# 02.net
KiCad netlist of a schematic drawn in Altium Designer
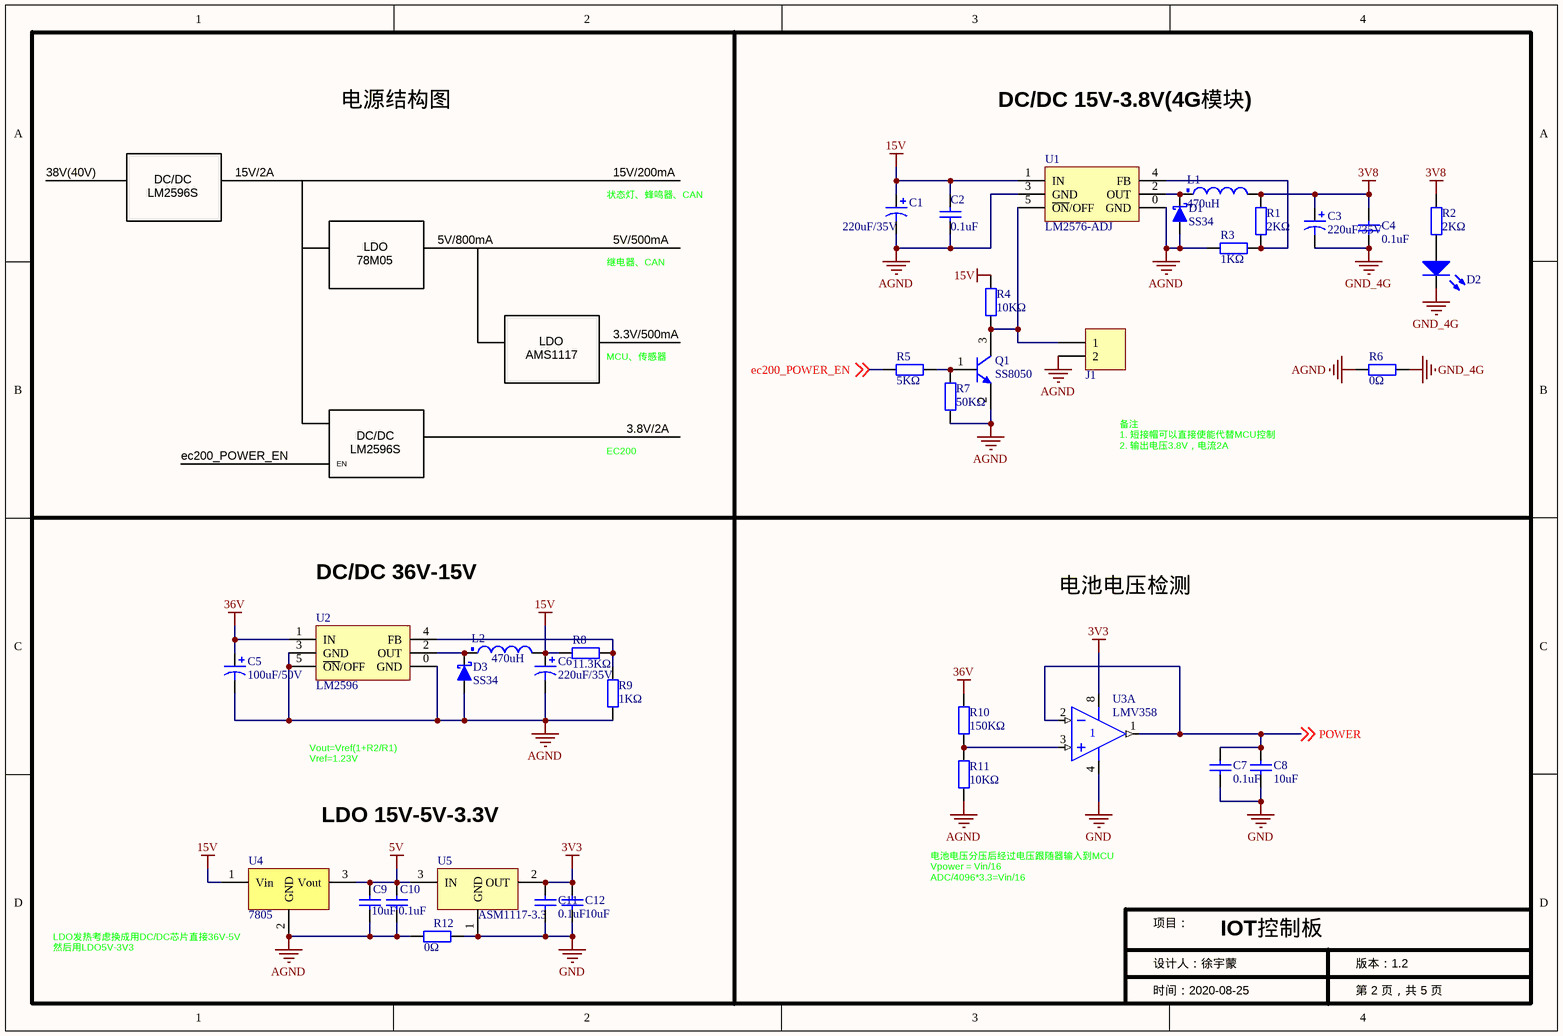
[diagram p0: 02_电源部分.SchDoc]

(export (version "E")
  (design (tool "Eeschema 10.0.6"))
  (components
    (comp (ref "C1")
      (value "220uF/35V")
      (footprint "Cap8x10.5mm")
      (description "贴片电解电容 8*10.5mm")
      (fields (field (name "Comment") "Cap Pol") (field (name "PUBLISHER") "Altium Limited"))
      (libsource (lib "元件库") (part "Cap Pol"))
    )
    (comp (ref "C2")
      (value "0.1uF")
      (footprint "CAP-0603")
      (description "无极性电容")
      (fields (field (name "Comment") "Cap") (field (name "PUBLISHER") "Altium Limited"))
      (libsource (lib "Arrowy_Racing") (part "Cap"))
    )
    (comp (ref "C3")
      (value "220uF/35V")
      (footprint "Cap8x10.5mm")
      (description "贴片电解电容 8*10.5mm")
      (fields (field (name "Comment") "Cap Pol") (field (name "PUBLISHER") "Altium Limited"))
      (libsource (lib "元件库") (part "Cap Pol"))
    )
    (comp (ref "C4")
      (value "0.1uF")
      (footprint "CAP-0603")
      (description "无极性电容")
      (fields (field (name "Comment") "Cap") (field (name "PUBLISHER") "Altium Limited"))
      (libsource (lib "Arrowy_Racing") (part "Cap"))
    )
    (comp (ref "C5")
      (value "100uF/50V")
      (footprint "Cap8x10.5mm")
      (description "贴片电解电容 8*10.5mm")
      (fields (field (name "Comment") "Cap Pol") (field (name "PUBLISHER") "Altium Limited"))
      (libsource (lib "元件库") (part "Cap Pol"))
    )
    (comp (ref "C6")
      (value "220uF/35V")
      (footprint "Cap8x10.5mm")
      (description "贴片电解电容 8*10.5mm")
      (fields (field (name "Comment") "Cap Pol") (field (name "PUBLISHER") "Altium Limited"))
      (libsource (lib "元件库") (part "Cap Pol"))
    )
    (comp (ref "C7")
      (value "0.1uF")
      (footprint "CAP-0603")
      (description "无极性电容")
      (fields (field (name "Comment") "Cap") (field (name "PUBLISHER") "Altium Limited"))
      (libsource (lib "Arrowy_Racing") (part "Cap"))
    )
    (comp (ref "C8")
      (value "10uF")
      (footprint "CAP-0603")
      (description "无极性电容")
      (fields (field (name "Comment") "Cap") (field (name "PUBLISHER") "Altium Limited"))
      (libsource (lib "Arrowy_Racing") (part "Cap"))
    )
    (comp (ref "C9")
      (value "10uF")
      (footprint "CAP-0603")
      (description "无极性电容")
      (fields (field (name "Comment") "Cap") (field (name "PUBLISHER") "Altium Limited"))
      (libsource (lib "Arrowy_Racing") (part "Cap"))
    )
    (comp (ref "C10")
      (value "0.1uF")
      (footprint "CAP-0603")
      (description "无极性电容")
      (fields (field (name "Comment") "Cap") (field (name "PUBLISHER") "Altium Limited"))
      (libsource (lib "Arrowy_Racing") (part "Cap"))
    )
    (comp (ref "C11")
      (value "0.1uF")
      (footprint "CAP-0603")
      (description "无极性电容")
      (fields (field (name "Comment") "Cap") (field (name "PUBLISHER") "Altium Limited"))
      (libsource (lib "Arrowy_Racing") (part "Cap"))
    )
    (comp (ref "C12")
      (value "10uF")
      (footprint "CAP-0603")
      (description "无极性电容")
      (fields (field (name "Comment") "Cap") (field (name "PUBLISHER") "Altium Limited"))
      (libsource (lib "Arrowy_Racing") (part "Cap"))
    )
    (comp (ref "D1")
      (value "SS34")
      (footprint "SMA(DO-214AC)")
      (description "Schottky Diode")
      (fields (field (name "PUBLISHER") "Altium Limited"))
      (libsource (lib "元件库") (part "D Schottky"))
    )
    (comp (ref "D2")
      (value "LED")
      (footprint "LED_0805")
      (description "发光二极管")
      (fields (field (name "PUBLISHER") "Altium Limited"))
      (libsource (lib "Arrowy_Racing") (part "LED"))
    )
    (comp (ref "D3")
      (value "SS34")
      (footprint "SMA(DO-214AC)")
      (description "Schottky Diode")
      (fields (field (name "PUBLISHER") "Altium Limited"))
      (libsource (lib "元件库") (part "D Schottky"))
    )
    (comp (ref "J1")
      (value "Header 2")
      (footprint "Header_2X1_2.54")
      (description "接插件")
      (fields (field (name "PUBLISHER") "Altium Limited"))
      (libsource (lib "Arrowy_Racing") (part "Header 2"))
    )
    (comp (ref "L1")
      (value "470uH")
      (footprint "CD43")
      (description "贴片功率电感")
      (fields (field (name "Comment") "Inductor") (field (name "PUBLISHER") "Altium Limited"))
      (libsource (lib "元件库") (part "Inductor"))
    )
    (comp (ref "L2")
      (value "470uH")
      (footprint "CD43")
      (description "贴片功率电感")
      (fields (field (name "Comment") "Inductor") (field (name "PUBLISHER") "Altium Limited"))
      (libsource (lib "元件库") (part "Inductor"))
    )
    (comp (ref "Q1")
      (value "SS8050")
      (footprint "SOT-23")
      (description "NPN贴片三极管")
      (fields (field (name "PUBLISHER") "Altium Limited"))
      (libsource (lib "Arrowy_Racing") (part "SS8050"))
    )
    (comp (ref "R1")
      (value "2KΩ")
      (footprint "0603")
      (description "贴片电阻")
      (fields (field (name "Comment") "Res") (field (name "PUBLISHER") "Altium Limited"))
      (libsource (lib "") (part "Res_2"))
    )
    (comp (ref "R2")
      (value "2KΩ")
      (footprint "0603")
      (description "贴片电阻")
      (fields (field (name "Comment") "Res") (field (name "PUBLISHER") "Altium Limited"))
      (libsource (lib "Arrowy_Racing") (part "Res"))
    )
    (comp (ref "R3")
      (value "1KΩ")
      (footprint "0603")
      (description "贴片电阻")
      (fields (field (name "Comment") "Res") (field (name "PUBLISHER") "Altium Limited"))
      (libsource (lib "") (part "Res_1"))
    )
    (comp (ref "R4")
      (value "10KΩ")
      (footprint "0603")
      (description "贴片电阻")
      (fields (field (name "Comment") "Res") (field (name "PUBLISHER") "Altium Limited"))
      (libsource (lib "") (part "Res_2"))
    )
    (comp (ref "R5")
      (value "5KΩ")
      (footprint "0603")
      (description "贴片电阻")
      (fields (field (name "Comment") "Res") (field (name "PUBLISHER") "Altium Limited"))
      (libsource (lib "") (part "Res_1"))
    )
    (comp (ref "R6")
      (value "0Ω")
      (footprint "0805")
      (description "贴片电阻")
      (fields (field (name "Comment") "Res") (field (name "PUBLISHER") "Altium Limited"))
      (libsource (lib "") (part "Res_1"))
    )
    (comp (ref "R7")
      (value "50KΩ")
      (footprint "0603")
      (description "贴片电阻")
      (fields (field (name "Comment") "Res") (field (name "PUBLISHER") "Altium Limited"))
      (libsource (lib "") (part "Res_2"))
    )
    (comp (ref "R8")
      (value "11.3KΩ")
      (footprint "0603")
      (description "贴片电阻")
      (fields (field (name "Comment") "Res") (field (name "PUBLISHER") "Altium Limited"))
      (libsource (lib "") (part "Res_1"))
    )
    (comp (ref "R9")
      (value "1KΩ")
      (footprint "0603")
      (description "贴片电阻")
      (fields (field (name "Comment") "Res") (field (name "PUBLISHER") "Altium Limited"))
      (libsource (lib "Arrowy_Racing") (part "Res"))
    )
    (comp (ref "R10")
      (value "150KΩ")
      (footprint "0603")
      (description "贴片电阻")
      (fields (field (name "Comment") "Res") (field (name "PUBLISHER") "Altium Limited"))
      (libsource (lib "Arrowy_Racing") (part "Res"))
    )
    (comp (ref "R11")
      (value "10KΩ")
      (footprint "0603")
      (description "贴片电阻")
      (fields (field (name "Comment") "Res") (field (name "PUBLISHER") "Altium Limited"))
      (libsource (lib "Arrowy_Racing") (part "Res"))
    )
    (comp (ref "R12")
      (value "0Ω")
      (footprint "0805")
      (description "贴片电阻")
      (fields (field (name "Comment") "Res") (field (name "PUBLISHER") "Altium Limited"))
      (libsource (lib "") (part "Res_1"))
    )
    (comp (ref "U1")
      (value "LM2576-ADJ")
      (footprint "TO-263-5 无背面散热")
      (libsource (lib "Arrowy_Racing") (part "LM2576"))
    )
    (comp (ref "U2")
      (value "LM2596")
      (footprint "TO-263-5 无背面散热")
      (description "DC/DC")
      (libsource (lib "Arrowy_Racing") (part "LM2596"))
    )
    (comp (ref "U3")
      (value "LMV358")
      (footprint "OPA2350")
      (fields (field (name "PUBLISHER") "Altium Limited"))
      (libsource (lib "元件库") (part "LMV358"))
    )
    (comp (ref "U4")
      (value "7805")
      (footprint "TO-252")
      (description "三端稳压器7805")
      (libsource (lib "Arrowy_Racing") (part "7805"))
    )
    (comp (ref "U5")
      (value "ASM1117-3.3")
      (footprint "SOT-223")
      (description "3.3V稳压芯片")
      (libsource (lib "Arrowy_Racing") (part "ASM1117"))
    )
  )
  (nets
    (net (code "1") (name "3V3") (class "Default")
      (node (ref "C11") (pin "2") (pinfunction "2_2") (pintype "passive"))
      (node (ref "C12") (pin "2") (pinfunction "2_2") (pintype "passive"))
      (node (ref "U3") (pin "8") (pinfunction "V+_8") (pintype "power_in"))
      (node (ref "U5") (pin "2") (pinfunction "OUT_2") (pintype "passive"))
    )
    (net (code "2") (name "3V8") (class "Default")
      (node (ref "C3") (pin "1") (pinfunction "1_1") (pintype "passive"))
      (node (ref "C4") (pin "2") (pinfunction "2_2") (pintype "passive"))
      (node (ref "L1") (pin "2") (pinfunction "2_2") (pintype "passive"))
      (node (ref "R1") (pin "1") (pinfunction "1_1") (pintype "passive"))
      (node (ref "R2") (pin "2") (pinfunction "2_2") (pintype "passive"))
    )
    (net (code "3") (name "5V") (class "Default")
      (node (ref "C10") (pin "2") (pinfunction "2_2") (pintype "passive"))
      (node (ref "C9") (pin "2") (pinfunction "2_2") (pintype "passive"))
      (node (ref "U4") (pin "3") (pinfunction "Vout_3") (pintype "passive"))
      (node (ref "U5") (pin "3") (pinfunction "IN_3") (pintype "passive"))
    )
    (net (code "4") (name "15V") (class "Default")
      (node (ref "C1") (pin "1") (pinfunction "1_1") (pintype "passive"))
      (node (ref "C2") (pin "2") (pinfunction "2_2") (pintype "passive"))
      (node (ref "C6") (pin "1") (pinfunction "1_1") (pintype "passive"))
      (node (ref "L2") (pin "2") (pinfunction "2_2") (pintype "passive"))
      (node (ref "R4") (pin "1") (pinfunction "1_1") (pintype "passive"))
      (node (ref "R8") (pin "1") (pinfunction "1_1") (pintype "passive"))
      (node (ref "U1") (pin "1") (pinfunction "IN_1") (pintype "passive"))
      (node (ref "U4") (pin "1") (pinfunction "Vin_1") (pintype "passive"))
    )
    (net (code "5") (name "36V") (class "Default")
      (node (ref "C5") (pin "1") (pinfunction "1_1") (pintype "passive"))
      (node (ref "R10") (pin "2") (pinfunction "2_2") (pintype "passive"))
      (node (ref "U2") (pin "1") (pinfunction "IN_1") (pintype "passive"))
    )
    (net (code "6") (name "AGND") (class "Default")
      (node (ref "C1") (pin "2") (pinfunction "2_2") (pintype "passive"))
      (node (ref "C10") (pin "1") (pinfunction "1_1") (pintype "passive"))
      (node (ref "C2") (pin "1") (pinfunction "1_1") (pintype "passive"))
      (node (ref "C5") (pin "2") (pinfunction "2_2") (pintype "passive"))
      (node (ref "C6") (pin "2") (pinfunction "2_2") (pintype "passive"))
      (node (ref "C9") (pin "1") (pinfunction "1_1") (pintype "passive"))
      (node (ref "D1") (pin "1") (pinfunction "A_1") (pintype "passive"))
      (node (ref "D3") (pin "1") (pinfunction "A_1") (pintype "passive"))
      (node (ref "J1") (pin "2") (pinfunction "2_2") (pintype "passive"))
      (node (ref "Q1") (pin "2") (pinfunction "E_2") (pintype "passive"))
      (node (ref "R11") (pin "1") (pinfunction "1_1") (pintype "passive"))
      (node (ref "R12") (pin "1") (pinfunction "1_1") (pintype "passive"))
      (node (ref "R3") (pin "1") (pinfunction "1_1") (pintype "passive"))
      (node (ref "R6") (pin "1") (pinfunction "1_1") (pintype "passive"))
      (node (ref "R7") (pin "2") (pinfunction "2_2") (pintype "passive"))
      (node (ref "R9") (pin "1") (pinfunction "1_1") (pintype "passive"))
      (node (ref "U1") (pin "0") (pinfunction "GND_0") (pintype "passive"))
      (node (ref "U1") (pin "3") (pinfunction "GND_3") (pintype "passive"))
      (node (ref "U2") (pin "0") (pinfunction "GND_0") (pintype "passive"))
      (node (ref "U2") (pin "3") (pinfunction "GND_3") (pintype "passive"))
      (node (ref "U2") (pin "5") (pinfunction "~{ON}/OFF_5") (pintype "passive"))
      (node (ref "U4") (pin "2") (pinfunction "GND_2") (pintype "passive"))
    )
    (net (code "7") (name "GND") (class "Default")
      (node (ref "C11") (pin "1") (pinfunction "1_1") (pintype "passive"))
      (node (ref "C12") (pin "1") (pinfunction "1_1") (pintype "passive"))
      (node (ref "C7") (pin "1") (pinfunction "1_1") (pintype "passive"))
      (node (ref "C8") (pin "1") (pinfunction "1_1") (pintype "passive"))
      (node (ref "R12") (pin "2") (pinfunction "2_2") (pintype "passive"))
      (node (ref "U3") (pin "4") (pinfunction "V-_4") (pintype "power_in"))
      (node (ref "U5") (pin "1") (pinfunction "GND_1") (pintype "passive"))
    )
    (net (code "8") (name "GND_4G") (class "Default")
      (node (ref "C3") (pin "2") (pinfunction "2_2") (pintype "passive"))
      (node (ref "C4") (pin "1") (pinfunction "1_1") (pintype "passive"))
      (node (ref "D2") (pin "2") (pinfunction "K_2") (pintype "passive"))
      (node (ref "R6") (pin "2") (pinfunction "2_2") (pintype "passive"))
    )
    (net (code "9") (name "Net-(D1-K)") (class "Default")
      (node (ref "D1") (pin "2") (pinfunction "K_2") (pintype "passive"))
      (node (ref "L1") (pin "1") (pinfunction "1_1") (pintype "passive"))
      (node (ref "U1") (pin "2") (pinfunction "OUT_2") (pintype "passive"))
    )
    (net (code "10") (name "Net-(D2-A)") (class "Default")
      (node (ref "D2") (pin "1") (pinfunction "A_1") (pintype "passive"))
      (node (ref "R2") (pin "1") (pinfunction "1_1") (pintype "passive"))
    )
    (net (code "11") (name "Net-(D3-K)") (class "Default")
      (node (ref "D3") (pin "2") (pinfunction "K_2") (pintype "passive"))
      (node (ref "L2") (pin "1") (pinfunction "1_1") (pintype "passive"))
      (node (ref "U2") (pin "2") (pinfunction "OUT_2") (pintype "passive"))
    )
    (net (code "12") (name "Net-(Q1-B)") (class "Default")
      (node (ref "Q1") (pin "1") (pinfunction "B_1") (pintype "passive"))
      (node (ref "R5") (pin "2") (pinfunction "2_2") (pintype "passive"))
      (node (ref "R7") (pin "1") (pinfunction "1_1") (pintype "passive"))
    )
    (net (code "13") (name "Net-(Q1-C)") (class "Default")
      (node (ref "J1") (pin "1") (pinfunction "1_1") (pintype "passive"))
      (node (ref "Q1") (pin "3") (pinfunction "C_3") (pintype "passive"))
      (node (ref "R4") (pin "2") (pinfunction "2_2") (pintype "passive"))
      (node (ref "U1") (pin "5") (pinfunction "~{ON}/OFF_5") (pintype "passive"))
    )
    (net (code "14") (name "Net-(U1-FB)") (class "Default")
      (node (ref "R1") (pin "2") (pinfunction "2_2") (pintype "passive"))
      (node (ref "R3") (pin "2") (pinfunction "2_2") (pintype "passive"))
      (node (ref "U1") (pin "4") (pinfunction "FB_4") (pintype "passive"))
    )
    (net (code "15") (name "Net-(U2-FB)") (class "Default")
      (node (ref "R8") (pin "2") (pinfunction "2_2") (pintype "passive"))
      (node (ref "R9") (pin "2") (pinfunction "2_2") (pintype "passive"))
      (node (ref "U2") (pin "4") (pinfunction "FB_4") (pintype "passive"))
    )
    (net (code "16") (name "Net-(U3A-IN+)") (class "Default")
      (node (ref "R10") (pin "1") (pinfunction "1_1") (pintype "passive"))
      (node (ref "R11") (pin "2") (pinfunction "2_2") (pintype "passive"))
      (node (ref "U3") (pin "3") (pinfunction "IN+_3") (pintype "input"))
    )
    (net (code "17") (name "POWER") (class "Default")
      (node (ref "C7") (pin "2") (pinfunction "2_2") (pintype "passive"))
      (node (ref "C8") (pin "2") (pinfunction "2_2") (pintype "passive"))
      (node (ref "U3") (pin "1") (pinfunction "OUT_1") (pintype "output"))
      (node (ref "U3") (pin "2") (pinfunction "IN-_2") (pintype "input"))
    )
    (net (code "18") (name "ec200_POWER_EN") (class "Default")
      (node (ref "R5") (pin "1") (pinfunction "1_1") (pintype "passive"))
    )
  )
)
